# openSX70-dongle_v3-1.net
KiCad netlist of a schematic drawn in EAGLE
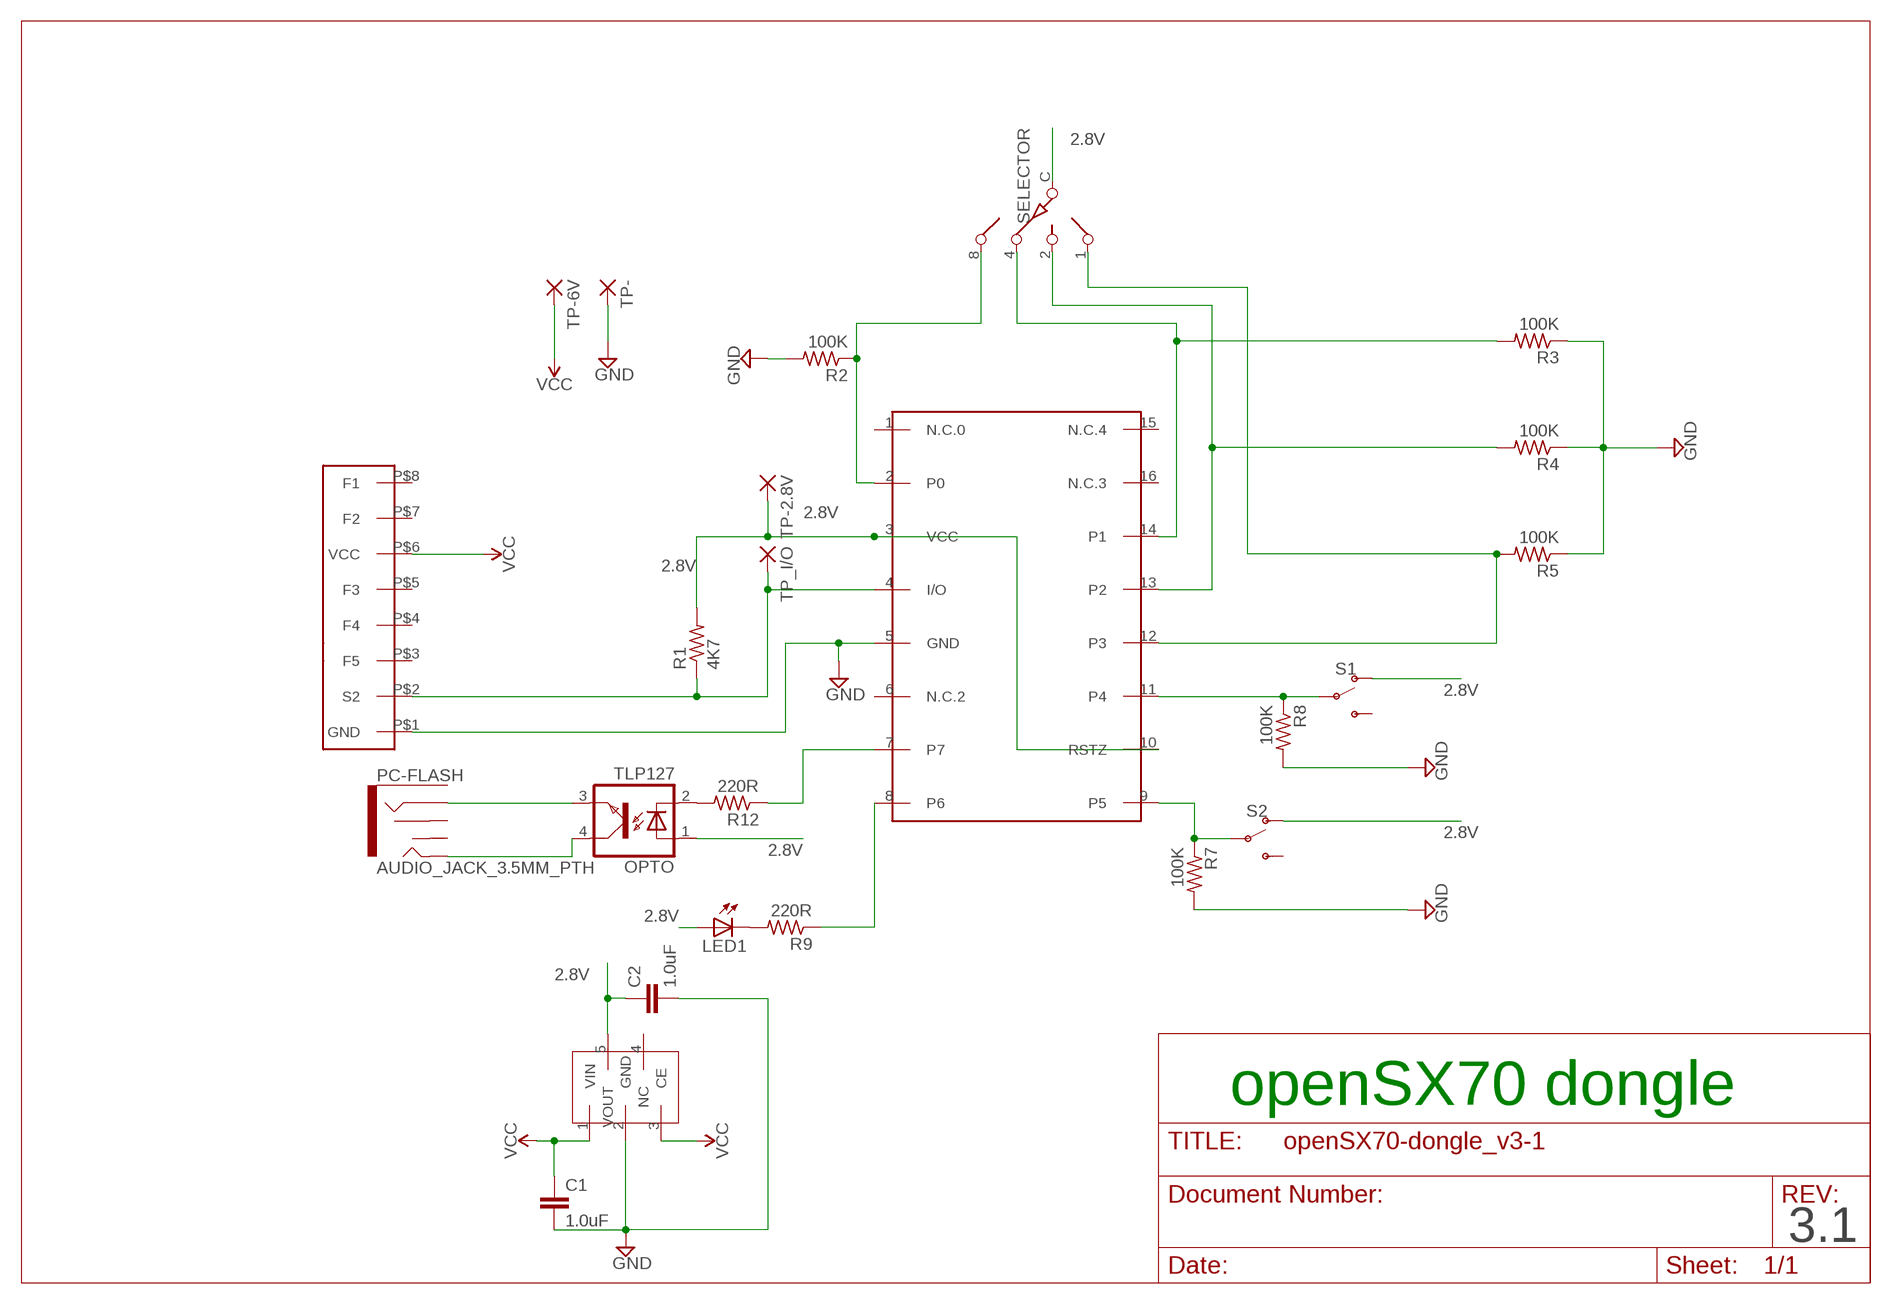
[diagram p0: schematic, sheet 1]

(export (version "E")
  (design (tool "Eeschema 10.0.6"))
  (components
    (comp (ref "C1")
      (value "1.0uF")
      (footprint "eagle-import:C0603")
      (libsource (lib "eagle-import") (part "C-EUC0603"))
    )
    (comp (ref "C2")
      (value "1.0uF")
      (footprint "eagle-import:C0603")
      (libsource (lib "eagle-import") (part "C-EUC0603"))
    )
    (comp (ref "DS2408")
      (value "DS2408")
      (footprint "eagle-import:SO16")
      (libsource (lib "eagle-import") (part "DS2408"))
    )
    (comp (ref "LED1")
      (value "LED3MM")
      (footprint "eagle-import:LED3MM")
      (libsource (lib "eagle-import") (part "LED3MM"))
    )
    (comp (ref "OPTO")
      (value "TLP127")
      (footprint "eagle-import:SO-4")
      (libsource (lib "eagle-import") (part "TLP127"))
    )
    (comp (ref "PC-FLASH")
      (value "AUDIO_JACK_3.5MM_PTH")
      (footprint "eagle-import:AUDIO-JACK")
      (libsource (lib "eagle-import") (part "AUDIO_JACK_3.5MM_PTH"))
    )
    (comp (ref "R1")
      (value "4K7")
      (footprint "eagle-import:M0805")
      (libsource (lib "eagle-import") (part "R-US_M0805"))
    )
    (comp (ref "R2")
      (value "100K")
      (footprint "eagle-import:M0805")
      (libsource (lib "eagle-import") (part "R-US_M0805"))
    )
    (comp (ref "R3")
      (value "100K")
      (footprint "eagle-import:M0805")
      (libsource (lib "eagle-import") (part "R-US_M0805"))
    )
    (comp (ref "R4")
      (value "100K")
      (footprint "eagle-import:M0805")
      (libsource (lib "eagle-import") (part "R-US_M0805"))
    )
    (comp (ref "R5")
      (value "100K")
      (footprint "eagle-import:M0805")
      (libsource (lib "eagle-import") (part "R-US_M0805"))
    )
    (comp (ref "R7")
      (value "100K")
      (footprint "eagle-import:M0805")
      (libsource (lib "eagle-import") (part "R-US_M0805"))
    )
    (comp (ref "R8")
      (value "100K")
      (footprint "eagle-import:M0805")
      (libsource (lib "eagle-import") (part "R-US_M0805"))
    )
    (comp (ref "R9")
      (value "220R")
      (footprint "eagle-import:M0805")
      (libsource (lib "eagle-import") (part "R-US_M0805"))
    )
    (comp (ref "R12")
      (value "220R")
      (footprint "eagle-import:M0805")
      (libsource (lib "eagle-import") (part "R-US_M0805"))
    )
    (comp (ref "REG")
      (value "NCP4688")
      (footprint "eagle-import:SOT-23-5")
      (libsource (lib "eagle-import") (part "NCP4688"))
    )
    (comp (ref "S1")
      (value "SWITCH-SPDT-SMD-RIGHT-ANGLE")
      (footprint "eagle-import:SWITCH_SPST_SMD_A")
      (libsource (lib "eagle-import") (part "SWITCH-SPDT-SMD-RIGHT-ANGLE"))
    )
    (comp (ref "S2")
      (value "SWITCH-SPDT-SMD-RIGHT-ANGLE")
      (footprint "eagle-import:SWITCH_SPST_SMD_A")
      (libsource (lib "eagle-import") (part "SWITCH-SPDT-SMD-RIGHT-ANGLE"))
    )
    (comp (ref "SELECTOR")
      (value "SW-C16")
      (footprint "eagle-import:SW-C16")
      (libsource (lib "eagle-import") (part "SW-C16"))
    )
    (comp (ref "TP-")
      (value "SMD2")
      (footprint "eagle-import:SMD1,27-2,54")
      (libsource (lib "eagle-import") (part "SMD2"))
    )
    (comp (ref "TP-2.8V")
      (value "SMD2")
      (footprint "eagle-import:SMD1,27-2,54")
      (libsource (lib "eagle-import") (part "SMD2"))
    )
    (comp (ref "TP-6V")
      (value "SMD2")
      (footprint "eagle-import:SMD1,27-2,54")
      (libsource (lib "eagle-import") (part "SMD2"))
    )
    (comp (ref "TP_I/O")
      (value "SMD2")
      (footprint "eagle-import:SMD1,27-2,54")
      (libsource (lib "eagle-import") (part "SMD2"))
    )
    (comp (ref "U$1")
      (value "FLASH-EDGE-CONNECTOR")
      (footprint "eagle-import:FLASH-EDGE-8")
      (libsource (lib "eagle-import") (part "FLASH-EDGE-CONNECTOR"))
    )
  )
  (nets
    (net (code "1") (name "/2.8V") (class "Default")
      (node (ref "C2") (pin "1") (pinfunction "1_1") (pintype "passive"))
      (node (ref "DS2408") (pin "10") (pinfunction "RSTZ_10") (pintype "bidirectional"))
      (node (ref "DS2408") (pin "3") (pinfunction "VCC_3") (pintype "bidirectional"))
      (node (ref "LED1") (pin "A") (pinfunction "A_A") (pintype "passive"))
      (node (ref "OPTO") (pin "1") (pinfunction "A_1") (pintype "passive"))
      (node (ref "R1") (pin "2") (pinfunction "2_2") (pintype "passive"))
      (node (ref "REG") (pin "5") (pinfunction "VOUT_5") (pintype "bidirectional"))
      (node (ref "S1") (pin "1") (pinfunction "O_1") (pintype "passive"))
      (node (ref "S2") (pin "1") (pinfunction "O_1") (pintype "passive"))
      (node (ref "SELECTOR") (pin "C") (pinfunction "C_C") (pintype "passive"))
      (node (ref "TP-2.8V") (pin "1") (pinfunction "P_1") (pintype "passive"))
    )
    (net (code "2") (name "GND") (class "Default")
      (node (ref "C1") (pin "2") (pinfunction "2_2") (pintype "passive"))
      (node (ref "C2") (pin "2") (pinfunction "2_2") (pintype "passive"))
      (node (ref "DS2408") (pin "5") (pinfunction "GND_5") (pintype "bidirectional"))
      (node (ref "R2") (pin "2") (pinfunction "2_2") (pintype "passive"))
      (node (ref "R3") (pin "1") (pinfunction "1_1") (pintype "passive"))
      (node (ref "R4") (pin "1") (pinfunction "1_1") (pintype "passive"))
      (node (ref "R5") (pin "1") (pinfunction "1_1") (pintype "passive"))
      (node (ref "R7") (pin "2") (pinfunction "2_2") (pintype "passive"))
      (node (ref "R8") (pin "2") (pinfunction "2_2") (pintype "passive"))
      (node (ref "REG") (pin "2") (pinfunction "GND_2") (pintype "bidirectional"))
      (node (ref "TP-") (pin "1") (pinfunction "P_1") (pintype "passive"))
      (node (ref "U$1") (pin "P$1") (pinfunction "GND_P$1") (pintype "bidirectional"))
    )
    (net (code "3") (name "Net-(DS2408-I{slash}O)") (class "Default")
      (node (ref "DS2408") (pin "4") (pinfunction "I/O_4") (pintype "bidirectional"))
      (node (ref "R1") (pin "1") (pinfunction "1_1") (pintype "passive"))
      (node (ref "TP_I/O") (pin "1") (pinfunction "P_1") (pintype "passive"))
      (node (ref "U$1") (pin "P$2") (pinfunction "S2_P$2") (pintype "bidirectional"))
    )
    (net (code "4") (name "Net-(DS2408-P0)") (class "Default")
      (node (ref "DS2408") (pin "2") (pinfunction "P0_2") (pintype "bidirectional"))
      (node (ref "R2") (pin "1") (pinfunction "1_1") (pintype "passive"))
      (node (ref "SELECTOR") (pin "8") (pinfunction "8_8") (pintype "passive"))
    )
    (net (code "5") (name "Net-(DS2408-P1)") (class "Default")
      (node (ref "DS2408") (pin "14") (pinfunction "P1_14") (pintype "bidirectional"))
      (node (ref "R3") (pin "2") (pinfunction "2_2") (pintype "passive"))
      (node (ref "SELECTOR") (pin "4") (pinfunction "4_4") (pintype "passive"))
    )
    (net (code "6") (name "Net-(DS2408-P2)") (class "Default")
      (node (ref "DS2408") (pin "13") (pinfunction "P2_13") (pintype "bidirectional"))
      (node (ref "R4") (pin "2") (pinfunction "2_2") (pintype "passive"))
      (node (ref "SELECTOR") (pin "2") (pinfunction "2_2") (pintype "passive"))
    )
    (net (code "7") (name "Net-(DS2408-P3)") (class "Default")
      (node (ref "DS2408") (pin "12") (pinfunction "P3_12") (pintype "bidirectional"))
      (node (ref "R5") (pin "2") (pinfunction "2_2") (pintype "passive"))
      (node (ref "SELECTOR") (pin "1") (pinfunction "1_1") (pintype "passive"))
    )
    (net (code "8") (name "Net-(DS2408-P4)") (class "Default")
      (node (ref "DS2408") (pin "11") (pinfunction "P4_11") (pintype "bidirectional"))
      (node (ref "R8") (pin "1") (pinfunction "1_1") (pintype "passive"))
      (node (ref "S1") (pin "2") (pinfunction "P_2") (pintype "passive"))
    )
    (net (code "9") (name "Net-(DS2408-P5)") (class "Default")
      (node (ref "DS2408") (pin "9") (pinfunction "P5_9") (pintype "bidirectional"))
      (node (ref "R7") (pin "1") (pinfunction "1_1") (pintype "passive"))
      (node (ref "S2") (pin "2") (pinfunction "P_2") (pintype "passive"))
    )
    (net (code "10") (name "Net-(DS2408-P6)") (class "Default")
      (node (ref "DS2408") (pin "8") (pinfunction "P6_8") (pintype "bidirectional"))
      (node (ref "R9") (pin "1") (pinfunction "1_1") (pintype "passive"))
    )
    (net (code "11") (name "Net-(DS2408-P7)") (class "Default")
      (node (ref "DS2408") (pin "7") (pinfunction "P7_7") (pintype "bidirectional"))
      (node (ref "R12") (pin "1") (pinfunction "1_1") (pintype "passive"))
    )
    (net (code "12") (name "Net-(LED1-C)") (class "Default")
      (node (ref "LED1") (pin "K") (pinfunction "C_K") (pintype "passive"))
      (node (ref "R9") (pin "2") (pinfunction "2_2") (pintype "passive"))
    )
    (net (code "13") (name "Net-(OPTO-C)") (class "Default")
      (node (ref "OPTO") (pin "2") (pinfunction "C_2") (pintype "passive"))
      (node (ref "R12") (pin "2") (pinfunction "2_2") (pintype "passive"))
    )
    (net (code "14") (name "Net-(OPTO-COL)") (class "Default")
      (node (ref "OPTO") (pin "4") (pinfunction "COL_4") (pintype "passive"))
      (node (ref "PC-FLASH") (pin "TIP") (pinfunction "TIP_TIP") (pintype "bidirectional"))
    )
    (net (code "15") (name "Net-(OPTO-EMIT)") (class "Default")
      (node (ref "OPTO") (pin "3") (pinfunction "EMIT_3") (pintype "passive"))
      (node (ref "PC-FLASH") (pin "RING") (pinfunction "RING_RING") (pintype "bidirectional"))
    )
    (net (code "16") (name "VCC") (class "Default")
      (node (ref "C1") (pin "1") (pinfunction "1_1") (pintype "passive"))
      (node (ref "REG") (pin "1") (pinfunction "VIN_1") (pintype "bidirectional"))
      (node (ref "REG") (pin "3") (pinfunction "CE_3") (pintype "bidirectional"))
      (node (ref "TP-6V") (pin "1") (pinfunction "P_1") (pintype "passive"))
      (node (ref "U$1") (pin "P$6") (pinfunction "VCC_P$6") (pintype "bidirectional"))
    )
    (net (code "17") (name "unconnected-(DS2408-N.C.0-Pad1)") (class "Default")
      (node (ref "DS2408") (pin "1") (pinfunction "N.C.0_1") (pintype "bidirectional"))
    )
    (net (code "18") (name "unconnected-(DS2408-N.C.2-Pad6)") (class "Default")
      (node (ref "DS2408") (pin "6") (pinfunction "N.C.2_6") (pintype "bidirectional"))
    )
    (net (code "19") (name "unconnected-(DS2408-N.C.3-Pad16)") (class "Default")
      (node (ref "DS2408") (pin "16") (pinfunction "N.C.3_16") (pintype "bidirectional"))
    )
    (net (code "20") (name "unconnected-(DS2408-N.C.4-Pad15)") (class "Default")
      (node (ref "DS2408") (pin "15") (pinfunction "N.C.4_15") (pintype "bidirectional"))
    )
    (net (code "21") (name "unconnected-(PC-FLASH-PadRSH)") (class "Default")
      (node (ref "PC-FLASH") (pin "RSH") (pinfunction "RSH_RSH") (pintype "bidirectional"))
    )
    (net (code "22") (name "unconnected-(PC-FLASH-PadSLEEVE)") (class "Default")
      (node (ref "PC-FLASH") (pin "SLEEVE") (pinfunction "SLEEVE_SLEEVE") (pintype "bidirectional"))
    )
    (net (code "23") (name "unconnected-(PC-FLASH-PadTSH)") (class "Default")
      (node (ref "PC-FLASH") (pin "TSH") (pinfunction "TSH_TSH") (pintype "bidirectional"))
    )
    (net (code "24") (name "unconnected-(REG-NC-Pad4)") (class "Default")
      (node (ref "REG") (pin "4") (pinfunction "NC_4") (pintype "bidirectional"))
    )
    (net (code "25") (name "unconnected-(S1-S-Pad3)") (class "Default")
      (node (ref "S1") (pin "3") (pinfunction "S_3") (pintype "passive"))
    )
    (net (code "26") (name "unconnected-(S2-S-Pad3)") (class "Default")
      (node (ref "S2") (pin "3") (pinfunction "S_3") (pintype "passive"))
    )
    (net (code "27") (name "unconnected-(U$1-F1-PadP$8)") (class "Default")
      (node (ref "U$1") (pin "P$8") (pinfunction "F1_P$8") (pintype "bidirectional"))
    )
    (net (code "28") (name "unconnected-(U$1-F2-PadP$7)") (class "Default")
      (node (ref "U$1") (pin "P$7") (pinfunction "F2_P$7") (pintype "bidirectional"))
    )
    (net (code "29") (name "unconnected-(U$1-F3-PadP$5)") (class "Default")
      (node (ref "U$1") (pin "P$5") (pinfunction "F3_P$5") (pintype "bidirectional"))
    )
    (net (code "30") (name "unconnected-(U$1-F4-PadP$4)") (class "Default")
      (node (ref "U$1") (pin "P$4") (pinfunction "F4_P$4") (pintype "bidirectional"))
    )
    (net (code "31") (name "unconnected-(U$1-F5-PadP$3)") (class "Default")
      (node (ref "U$1") (pin "P$3") (pinfunction "F5_P$3") (pintype "bidirectional"))
    )
  )
)
